# LISN-BZH.net
KiCad netlist of a schematic drawn in EAGLE
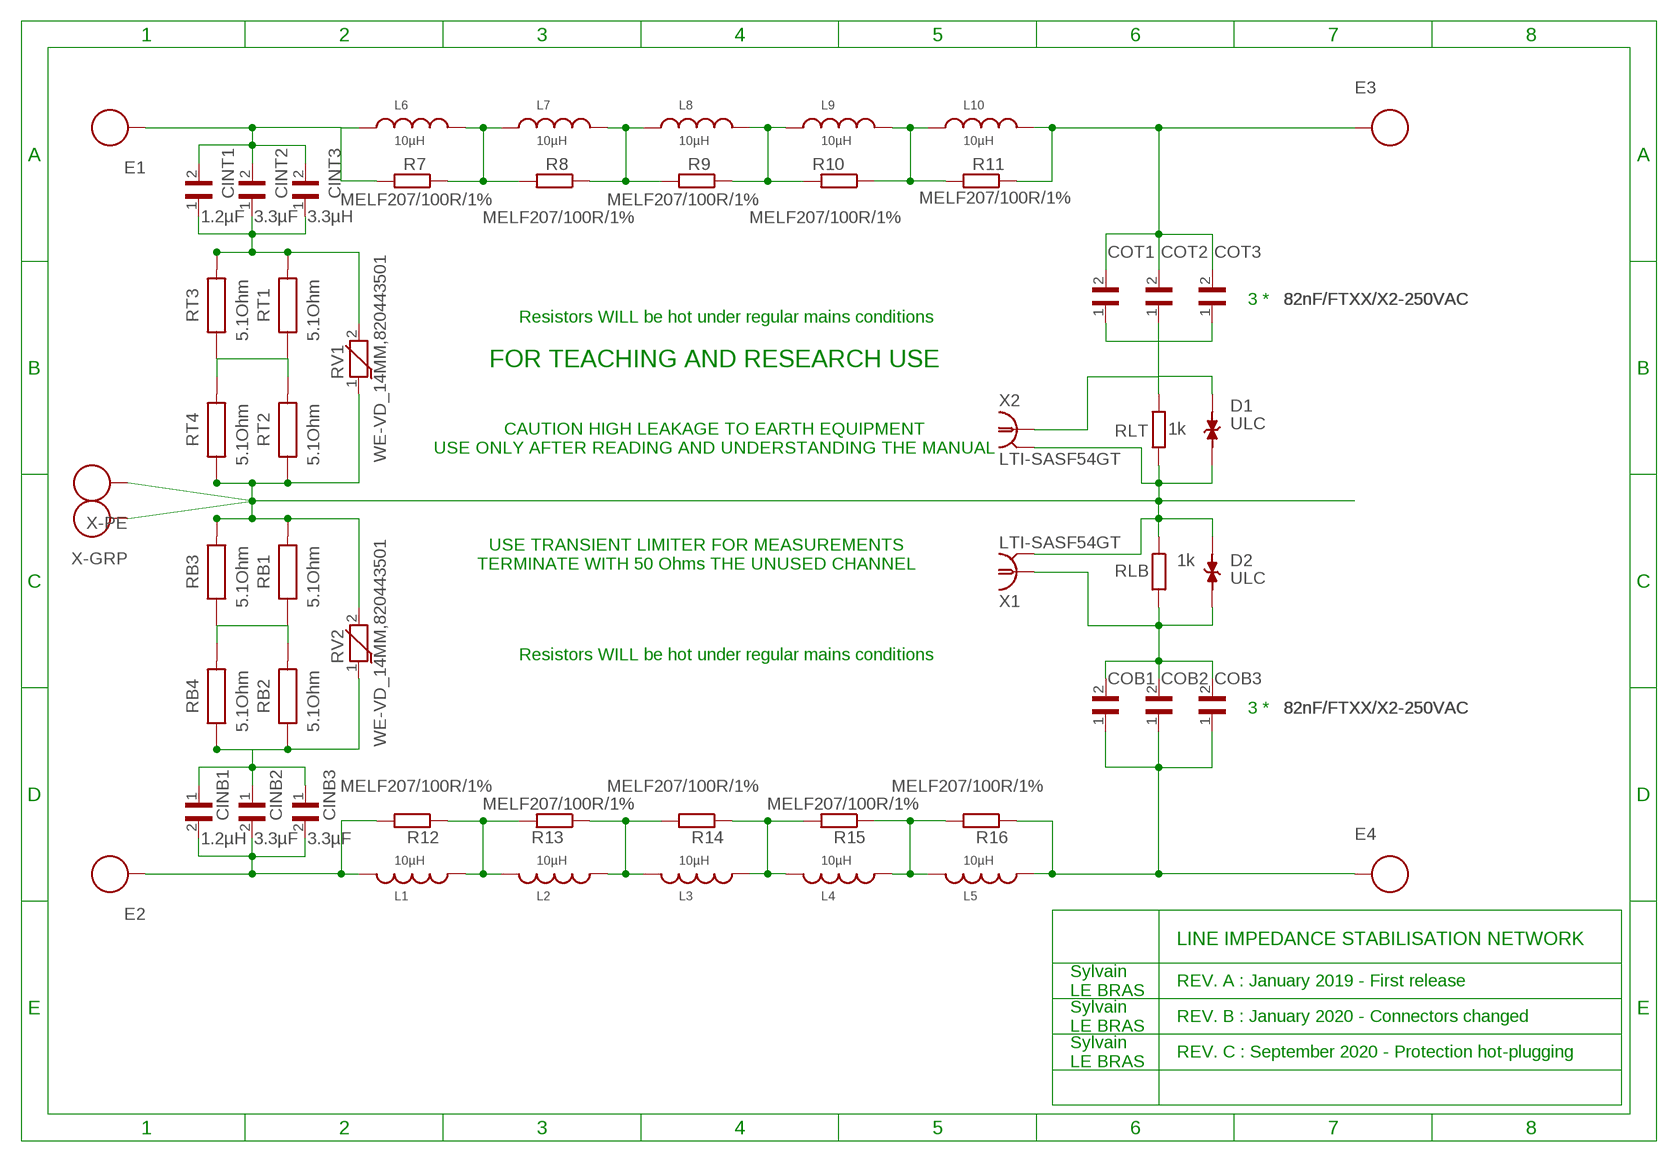
[diagram p0: schematic, sheet 1]

(export (version "E")
  (design (tool "Eeschema 10.0.6"))
  (components
    (comp (ref "CINB1")
      (value "1.2µH")
      (footprint "eagle-import:WCAP-FTXX_27.5X31X29X15.5")
      (libsource (lib "eagle-import") (part "WCAP-FTXX_890334027025"))
    )
    (comp (ref "CINB2")
      (value "3.3µF")
      (footprint "eagle-import:WCAP-FTXX_27.5X31X29X15.5")
      (libsource (lib "eagle-import") (part "WCAP-FTXX_890334027025"))
    )
    (comp (ref "CINB3")
      (value "3.3µF")
      (footprint "eagle-import:WCAP-FTXX_27.5X31X29X15.5")
      (libsource (lib "eagle-import") (part "WCAP-FTXX_890334027025"))
    )
    (comp (ref "CINT1")
      (value "1.2µF")
      (footprint "eagle-import:WCAP-FTXX_27.5X31X29X15.5")
      (libsource (lib "eagle-import") (part "WCAP-FTXX_890334027025"))
    )
    (comp (ref "CINT2")
      (value "3.3µF")
      (footprint "eagle-import:WCAP-FTXX_27.5X31X29X15.5")
      (libsource (lib "eagle-import") (part "WCAP-FTXX_890334027025"))
    )
    (comp (ref "CINT3")
      (value "3.3µH")
      (footprint "eagle-import:WCAP-FTXX_27.5X31X29X15.5")
      (libsource (lib "eagle-import") (part "WCAP-FTXX_890334027025"))
    )
    (comp (ref "COB1")
      (value "82nF/FTXX/X2-250VAC")
      (footprint "eagle-import:WCAP-FTXX_10X13X13X7")
      (libsource (lib "eagle-import") (part "WCAP-FTXX_890334023019"))
    )
    (comp (ref "COB2")
      (value "82nF/FTXX/X2-250VAC")
      (footprint "eagle-import:WCAP-FTXX_10X13X13X7")
      (libsource (lib "eagle-import") (part "WCAP-FTXX_890334023019"))
    )
    (comp (ref "COB3")
      (value "82nF/FTXX/X2-250VAC")
      (footprint "eagle-import:WCAP-FTXX_10X13X13X7")
      (libsource (lib "eagle-import") (part "WCAP-FTXX_890334023019"))
    )
    (comp (ref "COT1")
      (value "82nF/FTXX/X2-250VAC")
      (footprint "eagle-import:WCAP-FTXX_10X13X13X7")
      (libsource (lib "eagle-import") (part "WCAP-FTXX_890334023019"))
    )
    (comp (ref "COT2")
      (value "82nF/FTXX/X2-250VAC")
      (footprint "eagle-import:WCAP-FTXX_10X13X13X7")
      (libsource (lib "eagle-import") (part "WCAP-FTXX_890334023019"))
    )
    (comp (ref "COT3")
      (value "82nF/FTXX/X2-250VAC")
      (footprint "eagle-import:WCAP-FTXX_10X13X13X7")
      (libsource (lib "eagle-import") (part "WCAP-FTXX_890334023019"))
    )
    (comp (ref "D1")
      (value "ULC")
      (footprint "eagle-import:WE-VE_ULC_0603")
      (libsource (lib "eagle-import") (part "WE-VE_ULC_0603_82306050029"))
    )
    (comp (ref "D2")
      (value "ULC")
      (footprint "eagle-import:WE-VE_ULC_0603")
      (libsource (lib "eagle-import") (part "WE-VE_ULC_0603_82306050029"))
    )
    (comp (ref "E1")
      (value "WP-PLUG_7464000")
      (footprint "eagle-import:PLUG")
      (libsource (lib "eagle-import") (part "WP-PLUG_7464000"))
    )
    (comp (ref "E2")
      (value "WP-PLUG_7464000")
      (footprint "eagle-import:PLUG")
      (libsource (lib "eagle-import") (part "WP-PLUG_7464000"))
    )
    (comp (ref "E3")
      (value "WP-PLUG_7464000")
      (footprint "eagle-import:PLUG")
      (libsource (lib "eagle-import") (part "WP-PLUG_7464000"))
    )
    (comp (ref "E4")
      (value "WP-PLUG_7464000")
      (footprint "eagle-import:PLUG")
      (libsource (lib "eagle-import") (part "WP-PLUG_7464000"))
    )
    (comp (ref "L1")
      (value "10µH")
      (footprint "eagle-import:WE-HCC_1210")
      (libsource (lib "eagle-import") (part "WE-HCC_1210_7443321000"))
    )
    (comp (ref "L2")
      (value "10µH")
      (footprint "eagle-import:WE-HCC_1210")
      (libsource (lib "eagle-import") (part "WE-HCC_1210_7443321000"))
    )
    (comp (ref "L3")
      (value "10µH")
      (footprint "eagle-import:WE-HCC_1210")
      (libsource (lib "eagle-import") (part "WE-HCC_1210_7443321000"))
    )
    (comp (ref "L4")
      (value "10µH")
      (footprint "eagle-import:WE-HCC_1210")
      (libsource (lib "eagle-import") (part "WE-HCC_1210_7443321000"))
    )
    (comp (ref "L5")
      (value "10µH")
      (footprint "eagle-import:WE-HCC_1210")
      (libsource (lib "eagle-import") (part "WE-HCC_1210_7443321000"))
    )
    (comp (ref "L6")
      (value "10µH")
      (footprint "eagle-import:WE-HCC_1210")
      (libsource (lib "eagle-import") (part "WE-HCC_1210_7443321000"))
    )
    (comp (ref "L7")
      (value "10µH")
      (footprint "eagle-import:WE-HCC_1210")
      (libsource (lib "eagle-import") (part "WE-HCC_1210_7443321000"))
    )
    (comp (ref "L8")
      (value "10µH")
      (footprint "eagle-import:WE-HCC_1210")
      (libsource (lib "eagle-import") (part "WE-HCC_1210_7443321000"))
    )
    (comp (ref "L9")
      (value "10µH")
      (footprint "eagle-import:WE-HCC_1210")
      (libsource (lib "eagle-import") (part "WE-HCC_1210_7443321000"))
    )
    (comp (ref "L10")
      (value "10µH")
      (footprint "eagle-import:WE-HCC_1210")
      (libsource (lib "eagle-import") (part "WE-HCC_1210_7443321000"))
    )
    (comp (ref "R7")
      (value "MELF207/100R/1%")
      (footprint "eagle-import:MINI_MELF-0207R")
      (libsource (lib "eagle-import") (part "resistor_R-EU_MELF0207R"))
    )
    (comp (ref "R8")
      (value "MELF207/100R/1%")
      (footprint "eagle-import:MINI_MELF-0207R")
      (libsource (lib "eagle-import") (part "resistor_R-EU_MELF0207R"))
    )
    (comp (ref "R9")
      (value "MELF207/100R/1%")
      (footprint "eagle-import:MINI_MELF-0207R")
      (libsource (lib "eagle-import") (part "resistor_R-EU_MELF0207R"))
    )
    (comp (ref "R10")
      (value "MELF207/100R/1%")
      (footprint "eagle-import:MINI_MELF-0207R")
      (libsource (lib "eagle-import") (part "resistor_R-EU_MELF0207R"))
    )
    (comp (ref "R11")
      (value "MELF207/100R/1%")
      (footprint "eagle-import:MINI_MELF-0207R")
      (libsource (lib "eagle-import") (part "resistor_R-EU_MELF0207R"))
    )
    (comp (ref "R12")
      (value "MELF207/100R/1%")
      (footprint "eagle-import:MINI_MELF-0207R")
      (libsource (lib "eagle-import") (part "resistor_R-EU_MELF0207R"))
    )
    (comp (ref "R13")
      (value "MELF207/100R/1%")
      (footprint "eagle-import:MINI_MELF-0207R")
      (libsource (lib "eagle-import") (part "resistor_R-EU_MELF0207R"))
    )
    (comp (ref "R14")
      (value "MELF207/100R/1%")
      (footprint "eagle-import:MINI_MELF-0207R")
      (libsource (lib "eagle-import") (part "resistor_R-EU_MELF0207R"))
    )
    (comp (ref "R15")
      (value "MELF207/100R/1%")
      (footprint "eagle-import:MINI_MELF-0207R")
      (libsource (lib "eagle-import") (part "resistor_R-EU_MELF0207R"))
    )
    (comp (ref "R16")
      (value "MELF207/100R/1%")
      (footprint "eagle-import:MINI_MELF-0207R")
      (libsource (lib "eagle-import") (part "resistor_R-EU_MELF0207R"))
    )
    (comp (ref "RB1")
      (value "5.1Ohm")
      (footprint "eagle-import:WRIS-KWKB_1225")
      (libsource (lib "eagle-import") (part "WRIS-KWKB_1225_561020163017"))
    )
    (comp (ref "RB2")
      (value "5.1Ohm")
      (footprint "eagle-import:WRIS-KWKB_1225")
      (libsource (lib "eagle-import") (part "WRIS-KWKB_1225_561020163017"))
    )
    (comp (ref "RB3")
      (value "5.1Ohm")
      (footprint "eagle-import:WRIS-KWKB_1225")
      (libsource (lib "eagle-import") (part "WRIS-KWKB_1225_561020163017"))
    )
    (comp (ref "RB4")
      (value "5.1Ohm")
      (footprint "eagle-import:WRIS-KWKB_1225")
      (libsource (lib "eagle-import") (part "WRIS-KWKB_1225_561020163017"))
    )
    (comp (ref "RLB")
      (value "1k")
      (footprint "eagle-import:M0805")
      (libsource (lib "eagle-import") (part "R-EU_M0805"))
    )
    (comp (ref "RLT")
      (value "1k")
      (footprint "eagle-import:M0805")
      (libsource (lib "eagle-import") (part "R-EU_M0805"))
    )
    (comp (ref "RT1")
      (value "5.1Ohm")
      (footprint "eagle-import:WRIS-KWKB_1225")
      (libsource (lib "eagle-import") (part "WRIS-KWKB_1225_561020163017"))
    )
    (comp (ref "RT2")
      (value "5.1Ohm")
      (footprint "eagle-import:WRIS-KWKB_1225")
      (libsource (lib "eagle-import") (part "WRIS-KWKB_1225_561020163017"))
    )
    (comp (ref "RT3")
      (value "5.1Ohm")
      (footprint "eagle-import:WRIS-KWKB_1225")
      (libsource (lib "eagle-import") (part "WRIS-KWKB_1225_561020163017"))
    )
    (comp (ref "RT4")
      (value "5.1Ohm")
      (footprint "eagle-import:WRIS-KWKB_1225")
      (libsource (lib "eagle-import") (part "WRIS-KWKB_1225_561020163017"))
    )
    (comp (ref "RV1")
      (value "WE-VD_14MM,820443501")
      (footprint "eagle-import:WE-VD_14MM-0.9")
      (fields
        (field (name "MANUFACTURER") "Würth Elektronik eiSos GmbH")
        (field (name "CREATED-BY") "Christin Zierenner")
      )
      (libsource (lib "eagle-import") (part "WE-VD_14MM,820443501"))
    )
    (comp (ref "RV2")
      (value "WE-VD_14MM,820443501")
      (footprint "eagle-import:WE-VD_14MM-0.9")
      (fields
        (field (name "MANUFACTURER") "Würth Elektronik eiSos GmbH")
        (field (name "CREATED-BY") "Christin Zierenner")
      )
      (libsource (lib "eagle-import") (part "WE-VD_14MM,820443501"))
    )
    (comp (ref "X-GRP")
      (value "WP-THRSH_74651175(R)")
      (footprint "eagle-import:THRXU_1.85_4PINS_7X7")
      (libsource (lib "eagle-import") (part "WP-THRSH_74651175(R)"))
    )
    (comp (ref "X-PE")
      (value "WP-THRSH_74651175(R)")
      (footprint "eagle-import:THRXU_1.85_4PINS_7X7")
      (libsource (lib "eagle-import") (part "WP-THRSH_74651175(R)"))
    )
    (comp (ref "X1")
      (value "LTI-SASF54GT")
      (footprint "eagle-import:LTI-SASF54GT")
      (libsource (lib "eagle-import") (part "LTI-SASF54GT"))
    )
    (comp (ref "X2")
      (value "LTI-SASF54GT")
      (footprint "eagle-import:LTI-SASF54GT")
      (libsource (lib "eagle-import") (part "LTI-SASF54GT"))
    )
  )
  (nets
    (net (code "1") (name "Net-(CINB1-Pad1)") (class "Default")
      (node (ref "CINB1") (pin "1") (pinfunction "1_1") (pintype "passive"))
      (node (ref "CINB2") (pin "1") (pinfunction "1_1") (pintype "passive"))
      (node (ref "CINB3") (pin "1") (pinfunction "1_1") (pintype "passive"))
      (node (ref "RB2") (pin "1") (pinfunction "1_1") (pintype "passive"))
      (node (ref "RB4") (pin "1") (pinfunction "1_1") (pintype "passive"))
      (node (ref "RV2") (pin "1") (pinfunction "1_1") (pintype "passive"))
    )
    (net (code "2") (name "Net-(CINB1-Pad2)") (class "Default")
      (node (ref "CINB1") (pin "2") (pinfunction "2_2") (pintype "passive"))
      (node (ref "CINB2") (pin "2") (pinfunction "2_2") (pintype "passive"))
      (node (ref "CINB3") (pin "2") (pinfunction "2_2") (pintype "passive"))
      (node (ref "E2") (pin "1") (pinfunction "1_1") (pintype "passive"))
      (node (ref "E2") (pin "10") (pinfunction "1_10") (pintype "passive"))
      (node (ref "E2") (pin "11") (pinfunction "1_11") (pintype "passive"))
      (node (ref "E2") (pin "12") (pinfunction "1_12") (pintype "passive"))
      (node (ref "E2") (pin "2") (pinfunction "1_2") (pintype "passive"))
      (node (ref "E2") (pin "3") (pinfunction "1_3") (pintype "passive"))
      (node (ref "E2") (pin "4") (pinfunction "1_4") (pintype "passive"))
      (node (ref "E2") (pin "5") (pinfunction "1_5") (pintype "passive"))
      (node (ref "E2") (pin "6") (pinfunction "1_6") (pintype "passive"))
      (node (ref "E2") (pin "7") (pinfunction "1_7") (pintype "passive"))
      (node (ref "E2") (pin "8") (pinfunction "1_8") (pintype "passive"))
      (node (ref "E2") (pin "9") (pinfunction "1_9") (pintype "passive"))
      (node (ref "L1") (pin "1") (pinfunction "1_1") (pintype "passive"))
      (node (ref "R12") (pin "2") (pinfunction "2_2") (pintype "passive"))
    )
    (net (code "3") (name "Net-(CINT1-Pad1)") (class "Default")
      (node (ref "CINT1") (pin "1") (pinfunction "1_1") (pintype "passive"))
      (node (ref "CINT2") (pin "1") (pinfunction "1_1") (pintype "passive"))
      (node (ref "CINT3") (pin "1") (pinfunction "1_1") (pintype "passive"))
      (node (ref "RT1") (pin "2") (pinfunction "2_2") (pintype "passive"))
      (node (ref "RT3") (pin "2") (pinfunction "2_2") (pintype "passive"))
      (node (ref "RV1") (pin "2") (pinfunction "2_2") (pintype "passive"))
    )
    (net (code "4") (name "Net-(CINT1-Pad2)") (class "Default")
      (node (ref "CINT1") (pin "2") (pinfunction "2_2") (pintype "passive"))
      (node (ref "CINT2") (pin "2") (pinfunction "2_2") (pintype "passive"))
      (node (ref "CINT3") (pin "2") (pinfunction "2_2") (pintype "passive"))
      (node (ref "E1") (pin "1") (pinfunction "1_1") (pintype "passive"))
      (node (ref "E1") (pin "10") (pinfunction "1_10") (pintype "passive"))
      (node (ref "E1") (pin "11") (pinfunction "1_11") (pintype "passive"))
      (node (ref "E1") (pin "12") (pinfunction "1_12") (pintype "passive"))
      (node (ref "E1") (pin "2") (pinfunction "1_2") (pintype "passive"))
      (node (ref "E1") (pin "3") (pinfunction "1_3") (pintype "passive"))
      (node (ref "E1") (pin "4") (pinfunction "1_4") (pintype "passive"))
      (node (ref "E1") (pin "5") (pinfunction "1_5") (pintype "passive"))
      (node (ref "E1") (pin "6") (pinfunction "1_6") (pintype "passive"))
      (node (ref "E1") (pin "7") (pinfunction "1_7") (pintype "passive"))
      (node (ref "E1") (pin "8") (pinfunction "1_8") (pintype "passive"))
      (node (ref "E1") (pin "9") (pinfunction "1_9") (pintype "passive"))
      (node (ref "L6") (pin "1") (pinfunction "1_1") (pintype "passive"))
      (node (ref "R7") (pin "2") (pinfunction "2_2") (pintype "passive"))
    )
    (net (code "5") (name "Net-(COB1-Pad1)") (class "Default")
      (node (ref "COB1") (pin "1") (pinfunction "1_1") (pintype "passive"))
      (node (ref "COB2") (pin "1") (pinfunction "1_1") (pintype "passive"))
      (node (ref "COB3") (pin "1") (pinfunction "1_1") (pintype "passive"))
      (node (ref "E4") (pin "1") (pinfunction "1_1") (pintype "passive"))
      (node (ref "E4") (pin "10") (pinfunction "1_10") (pintype "passive"))
      (node (ref "E4") (pin "11") (pinfunction "1_11") (pintype "passive"))
      (node (ref "E4") (pin "12") (pinfunction "1_12") (pintype "passive"))
      (node (ref "E4") (pin "2") (pinfunction "1_2") (pintype "passive"))
      (node (ref "E4") (pin "3") (pinfunction "1_3") (pintype "passive"))
      (node (ref "E4") (pin "4") (pinfunction "1_4") (pintype "passive"))
      (node (ref "E4") (pin "5") (pinfunction "1_5") (pintype "passive"))
      (node (ref "E4") (pin "6") (pinfunction "1_6") (pintype "passive"))
      (node (ref "E4") (pin "7") (pinfunction "1_7") (pintype "passive"))
      (node (ref "E4") (pin "8") (pinfunction "1_8") (pintype "passive"))
      (node (ref "E4") (pin "9") (pinfunction "1_9") (pintype "passive"))
      (node (ref "L5") (pin "2") (pinfunction "2_2") (pintype "passive"))
      (node (ref "R16") (pin "1") (pinfunction "1_1") (pintype "passive"))
    )
    (net (code "6") (name "Net-(COB1-Pad2)") (class "Default")
      (node (ref "COB1") (pin "2") (pinfunction "2_2") (pintype "passive"))
      (node (ref "COB2") (pin "2") (pinfunction "2_2") (pintype "passive"))
      (node (ref "COB3") (pin "2") (pinfunction "2_2") (pintype "passive"))
      (node (ref "D2") (pin "1") (pinfunction "1_1") (pintype "passive"))
      (node (ref "RLB") (pin "2") (pinfunction "2_2") (pintype "passive"))
      (node (ref "X1") (pin "1") (pinfunction "1_1") (pintype "passive"))
    )
    (net (code "7") (name "Net-(COT1-Pad1)") (class "Default")
      (node (ref "COT1") (pin "1") (pinfunction "1_1") (pintype "passive"))
      (node (ref "COT2") (pin "1") (pinfunction "1_1") (pintype "passive"))
      (node (ref "COT3") (pin "1") (pinfunction "1_1") (pintype "passive"))
      (node (ref "D1") (pin "1") (pinfunction "1_1") (pintype "passive"))
      (node (ref "RLT") (pin "2") (pinfunction "2_2") (pintype "passive"))
      (node (ref "X2") (pin "1") (pinfunction "1_1") (pintype "passive"))
    )
    (net (code "8") (name "Net-(COT1-Pad2)") (class "Default")
      (node (ref "COT1") (pin "2") (pinfunction "2_2") (pintype "passive"))
      (node (ref "COT2") (pin "2") (pinfunction "2_2") (pintype "passive"))
      (node (ref "COT3") (pin "2") (pinfunction "2_2") (pintype "passive"))
      (node (ref "E3") (pin "1") (pinfunction "1_1") (pintype "passive"))
      (node (ref "E3") (pin "10") (pinfunction "1_10") (pintype "passive"))
      (node (ref "E3") (pin "11") (pinfunction "1_11") (pintype "passive"))
      (node (ref "E3") (pin "12") (pinfunction "1_12") (pintype "passive"))
      (node (ref "E3") (pin "2") (pinfunction "1_2") (pintype "passive"))
      (node (ref "E3") (pin "3") (pinfunction "1_3") (pintype "passive"))
      (node (ref "E3") (pin "4") (pinfunction "1_4") (pintype "passive"))
      (node (ref "E3") (pin "5") (pinfunction "1_5") (pintype "passive"))
      (node (ref "E3") (pin "6") (pinfunction "1_6") (pintype "passive"))
      (node (ref "E3") (pin "7") (pinfunction "1_7") (pintype "passive"))
      (node (ref "E3") (pin "8") (pinfunction "1_8") (pintype "passive"))
      (node (ref "E3") (pin "9") (pinfunction "1_9") (pintype "passive"))
      (node (ref "L10") (pin "2") (pinfunction "2_2") (pintype "passive"))
      (node (ref "R11") (pin "1") (pinfunction "1_1") (pintype "passive"))
    )
    (net (code "9") (name "Net-(L1-Pad2)") (class "Default")
      (node (ref "L1") (pin "2") (pinfunction "2_2") (pintype "passive"))
      (node (ref "L2") (pin "1") (pinfunction "1_1") (pintype "passive"))
      (node (ref "R12") (pin "1") (pinfunction "1_1") (pintype "passive"))
      (node (ref "R13") (pin "2") (pinfunction "2_2") (pintype "passive"))
    )
    (net (code "10") (name "Net-(L2-Pad2)") (class "Default")
      (node (ref "L2") (pin "2") (pinfunction "2_2") (pintype "passive"))
      (node (ref "L3") (pin "1") (pinfunction "1_1") (pintype "passive"))
      (node (ref "R13") (pin "1") (pinfunction "1_1") (pintype "passive"))
      (node (ref "R14") (pin "2") (pinfunction "2_2") (pintype "passive"))
    )
    (net (code "11") (name "Net-(L3-Pad2)") (class "Default")
      (node (ref "L3") (pin "2") (pinfunction "2_2") (pintype "passive"))
      (node (ref "L4") (pin "1") (pinfunction "1_1") (pintype "passive"))
      (node (ref "R14") (pin "1") (pinfunction "1_1") (pintype "passive"))
      (node (ref "R15") (pin "2") (pinfunction "2_2") (pintype "passive"))
    )
    (net (code "12") (name "Net-(L4-Pad2)") (class "Default")
      (node (ref "L4") (pin "2") (pinfunction "2_2") (pintype "passive"))
      (node (ref "L5") (pin "1") (pinfunction "1_1") (pintype "passive"))
      (node (ref "R15") (pin "1") (pinfunction "1_1") (pintype "passive"))
      (node (ref "R16") (pin "2") (pinfunction "2_2") (pintype "passive"))
    )
    (net (code "13") (name "Net-(L6-Pad2)") (class "Default")
      (node (ref "L6") (pin "2") (pinfunction "2_2") (pintype "passive"))
      (node (ref "L7") (pin "1") (pinfunction "1_1") (pintype "passive"))
      (node (ref "R7") (pin "1") (pinfunction "1_1") (pintype "passive"))
      (node (ref "R8") (pin "2") (pinfunction "2_2") (pintype "passive"))
    )
    (net (code "14") (name "Net-(L7-Pad2)") (class "Default")
      (node (ref "L7") (pin "2") (pinfunction "2_2") (pintype "passive"))
      (node (ref "L8") (pin "1") (pinfunction "1_1") (pintype "passive"))
      (node (ref "R8") (pin "1") (pinfunction "1_1") (pintype "passive"))
      (node (ref "R9") (pin "2") (pinfunction "2_2") (pintype "passive"))
    )
    (net (code "15") (name "Net-(L8-Pad2)") (class "Default")
      (node (ref "L8") (pin "2") (pinfunction "2_2") (pintype "passive"))
      (node (ref "L9") (pin "1") (pinfunction "1_1") (pintype "passive"))
      (node (ref "R10") (pin "2") (pinfunction "2_2") (pintype "passive"))
      (node (ref "R9") (pin "1") (pinfunction "1_1") (pintype "passive"))
    )
    (net (code "16") (name "Net-(L10-Pad1)") (class "Default")
      (node (ref "L10") (pin "1") (pinfunction "1_1") (pintype "passive"))
      (node (ref "L9") (pin "2") (pinfunction "2_2") (pintype "passive"))
      (node (ref "R10") (pin "1") (pinfunction "1_1") (pintype "passive"))
      (node (ref "R11") (pin "2") (pinfunction "2_2") (pintype "passive"))
    )
    (net (code "17") (name "Net-(RB1-Pad1)") (class "Default")
      (node (ref "RB1") (pin "1") (pinfunction "1_1") (pintype "passive"))
      (node (ref "RB2") (pin "2") (pinfunction "2_2") (pintype "passive"))
      (node (ref "RB3") (pin "1") (pinfunction "1_1") (pintype "passive"))
      (node (ref "RB4") (pin "2") (pinfunction "2_2") (pintype "passive"))
    )
    (net (code "18") (name "Net-(RT1-Pad1)") (class "Default")
      (node (ref "RT1") (pin "1") (pinfunction "1_1") (pintype "passive"))
      (node (ref "RT2") (pin "2") (pinfunction "2_2") (pintype "passive"))
      (node (ref "RT3") (pin "1") (pinfunction "1_1") (pintype "passive"))
      (node (ref "RT4") (pin "2") (pinfunction "2_2") (pintype "passive"))
    )
    (net (code "19") (name "Net-(X1B-GND)") (class "Default")
      (node (ref "D1") (pin "2") (pinfunction "2_2") (pintype "passive"))
      (node (ref "D2") (pin "2") (pinfunction "2_2") (pintype "passive"))
      (node (ref "RB1") (pin "2") (pinfunction "2_2") (pintype "passive"))
      (node (ref "RB3") (pin "2") (pinfunction "2_2") (pintype "passive"))
      (node (ref "RLB") (pin "1") (pinfunction "1_1") (pintype "passive"))
      (node (ref "RLT") (pin "1") (pinfunction "1_1") (pintype "passive"))
      (node (ref "RT2") (pin "1") (pinfunction "1_1") (pintype "passive"))
      (node (ref "RT4") (pin "1") (pinfunction "1_1") (pintype "passive"))
      (node (ref "RV1") (pin "1") (pinfunction "1_1") (pintype "passive"))
      (node (ref "RV2") (pin "2") (pinfunction "2_2") (pintype "passive"))
      (node (ref "X-GRP") (pin "1") (pinfunction "1_1") (pintype "passive"))
      (node (ref "X-GRP") (pin "2") (pinfunction "1_2") (pintype "passive"))
      (node (ref "X-GRP") (pin "3") (pinfunction "1_3") (pintype "passive"))
      (node (ref "X-GRP") (pin "4") (pinfunction "1_4") (pintype "passive"))
      (node (ref "X-PE") (pin "1") (pinfunction "1_1") (pintype "passive"))
      (node (ref "X-PE") (pin "2") (pinfunction "1_2") (pintype "passive"))
      (node (ref "X-PE") (pin "3") (pinfunction "1_3") (pintype "passive"))
      (node (ref "X-PE") (pin "4") (pinfunction "1_4") (pintype "passive"))
      (node (ref "X1") (pin "2") (pinfunction "GND_2") (pintype "power_in"))
      (node (ref "X2") (pin "2") (pinfunction "GND_2") (pintype "power_in"))
    )
  )
)
